# FPGA_Banks1.net
KiCad netlist of a schematic drawn in Altium Designer
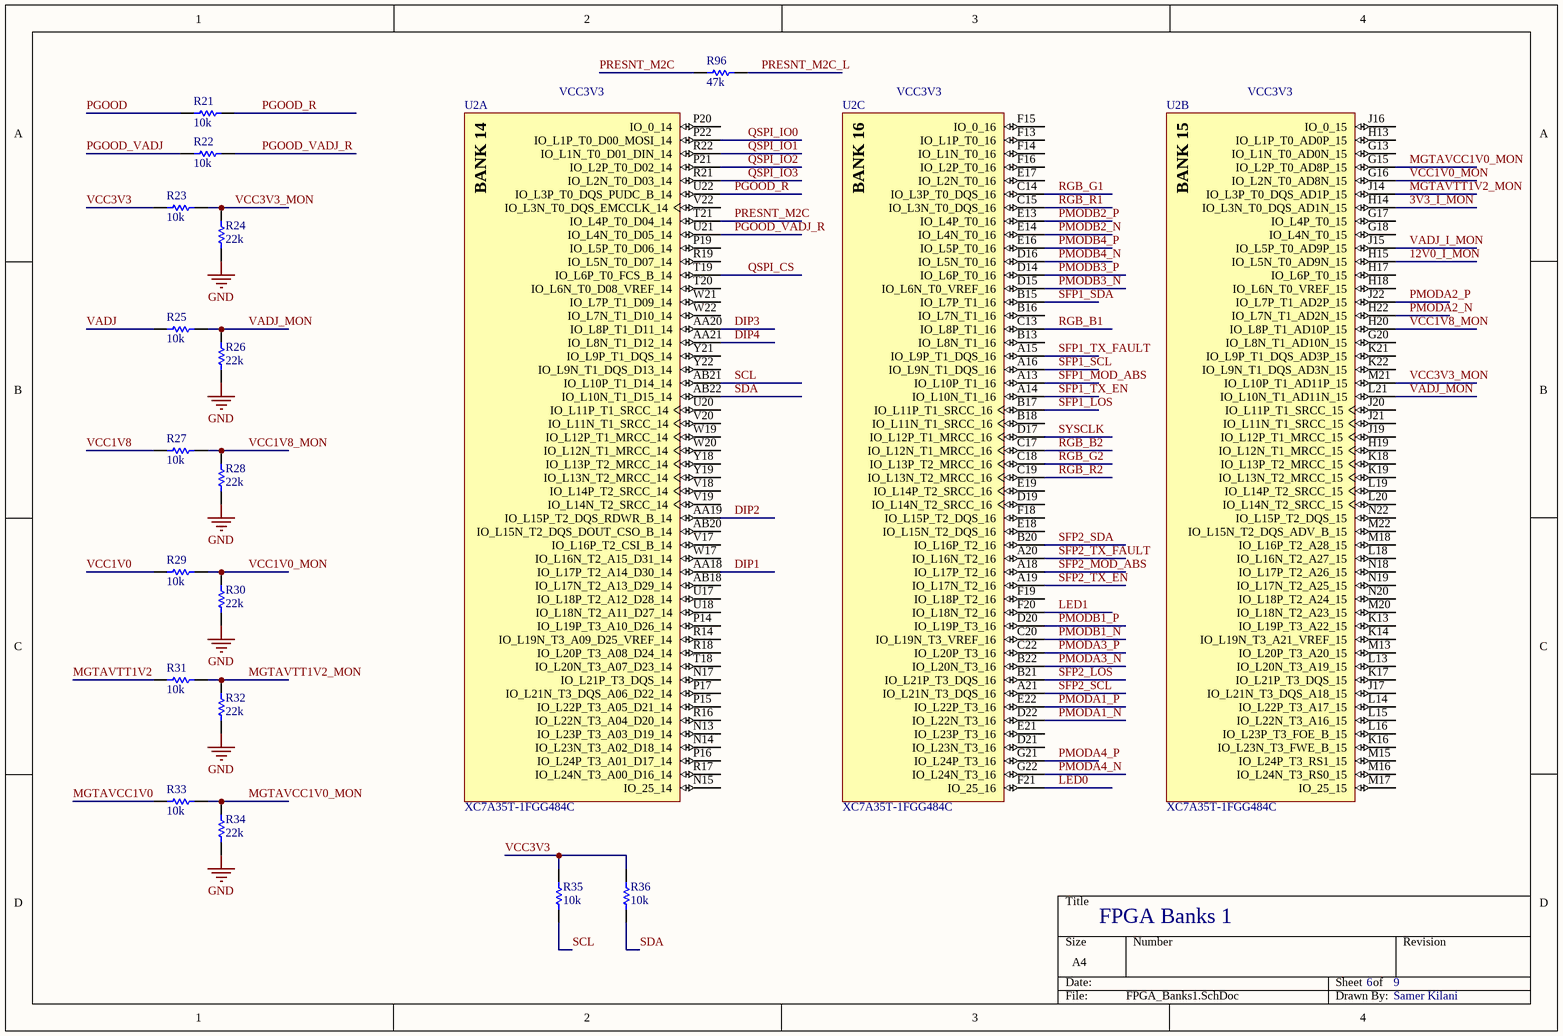
[diagram p0: FPGA_Banks1.SchDoc]

(export (version "E")
  (design (tool "Eeschema 10.0.6"))
  (components
    (comp (ref "R21")
      (value "10k")
      (footprint "R0402")
      (description "Resistor")
      (fields (field (name "Comment") "Res"))
      (libsource (lib "atfclib") (part "Res"))
    )
    (comp (ref "R22")
      (value "10k")
      (footprint "R0402")
      (description "Resistor")
      (fields (field (name "Comment") "Res"))
      (libsource (lib "atfclib") (part "Res"))
    )
    (comp (ref "R23")
      (value "10k")
      (footprint "R0402")
      (description "Resistor")
      (fields (field (name "Comment") "Res"))
      (libsource (lib "atfclib") (part "Res"))
    )
    (comp (ref "R24")
      (value "22k")
      (footprint "R0402")
      (description "Resistor")
      (fields (field (name "Comment") "Res"))
      (libsource (lib "atfclib") (part "Res"))
    )
    (comp (ref "R25")
      (value "10k")
      (footprint "R0402")
      (description "Resistor")
      (fields (field (name "Comment") "Res"))
      (libsource (lib "atfclib") (part "Res"))
    )
    (comp (ref "R26")
      (value "22k")
      (footprint "R0402")
      (description "Resistor")
      (fields (field (name "Comment") "Res"))
      (libsource (lib "atfclib") (part "Res"))
    )
    (comp (ref "R27")
      (value "10k")
      (footprint "R0402")
      (description "Resistor")
      (fields (field (name "Comment") "Res"))
      (libsource (lib "atfclib") (part "Res"))
    )
    (comp (ref "R28")
      (value "22k")
      (footprint "R0402")
      (description "Resistor")
      (fields (field (name "Comment") "Res"))
      (libsource (lib "atfclib") (part "Res"))
    )
    (comp (ref "R29")
      (value "10k")
      (footprint "R0402")
      (description "Resistor")
      (fields (field (name "Comment") "Res"))
      (libsource (lib "atfclib") (part "Res"))
    )
    (comp (ref "R30")
      (value "22k")
      (footprint "R0402")
      (description "Resistor")
      (fields (field (name "Comment") "Res"))
      (libsource (lib "atfclib") (part "Res"))
    )
    (comp (ref "R31")
      (value "10k")
      (footprint "R0402")
      (description "Resistor")
      (fields (field (name "Comment") "Res"))
      (libsource (lib "atfclib") (part "Res"))
    )
    (comp (ref "R32")
      (value "22k")
      (footprint "R0402")
      (description "Resistor")
      (fields (field (name "Comment") "Res"))
      (libsource (lib "atfclib") (part "Res"))
    )
    (comp (ref "R33")
      (value "10k")
      (footprint "R0402")
      (description "Resistor")
      (fields (field (name "Comment") "Res"))
      (libsource (lib "atfclib") (part "Res"))
    )
    (comp (ref "R34")
      (value "22k")
      (footprint "R0402")
      (description "Resistor")
      (fields (field (name "Comment") "Res"))
      (libsource (lib "atfclib") (part "Res"))
    )
    (comp (ref "R35")
      (value "10k")
      (footprint "R0402")
      (description "Resistor")
      (fields (field (name "Comment") "Res"))
      (libsource (lib "atfclib") (part "Res"))
    )
    (comp (ref "R36")
      (value "10k")
      (footprint "R0402")
      (description "Resistor")
      (fields (field (name "Comment") "Res"))
      (libsource (lib "atfclib") (part "Res"))
    )
    (comp (ref "R96")
      (value "47k")
      (footprint "R0402")
      (description "Resistor")
      (fields (field (name "Comment") "Res"))
      (libsource (lib "atfclib") (part "Res"))
    )
    (comp (ref "U2")
      (value "XC7A35T-1FGG484C")
      (footprint "FGG484")
      (description "Artix-7 FPGA, 250 User I/Os, 4 GTP, 484-Ball BGA, Speed Grade 1, Commercial Grade, Pb-Free")
      (fields (field (name "MANUFACTURER") "Xilinx"))
      (libsource (lib "atfclib") (part "XC7A35T-1FGG484C"))
    )
  )
  (nets
    (net (code "1") (name "/3V3_I_MON") (class "Default")
      (node (ref "U2") (pin "H14") (pinfunction "IO_L3N_T0_DQS_AD1N_15_H14") (pintype "bidirectional"))
    )
    (net (code "2") (name "/12V0_I_MON") (class "Default")
      (node (ref "U2") (pin "H15") (pinfunction "IO_L5N_T0_AD9N_15_H15") (pintype "bidirectional"))
    )
    (net (code "3") (name "/DIP1") (class "Default")
      (node (ref "U2") (pin "AA18") (pinfunction "IO_L17P_T2_A14_D30_14_AA18") (pintype "bidirectional"))
    )
    (net (code "4") (name "/DIP2") (class "Default")
      (node (ref "U2") (pin "AA19") (pinfunction "IO_L15P_T2_DQS_RDWR_B_14_AA19") (pintype "bidirectional"))
    )
    (net (code "5") (name "/DIP3") (class "Default")
      (node (ref "U2") (pin "AA20") (pinfunction "IO_L8P_T1_D11_14_AA20") (pintype "bidirectional"))
    )
    (net (code "6") (name "/DIP4") (class "Default")
      (node (ref "U2") (pin "AA21") (pinfunction "IO_L8N_T1_D12_14_AA21") (pintype "bidirectional"))
    )
    (net (code "7") (name "/LED0") (class "Default")
      (node (ref "U2") (pin "F21") (pinfunction "IO_25_16_F21") (pintype "bidirectional"))
    )
    (net (code "8") (name "/LED1") (class "Default")
      (node (ref "U2") (pin "F20") (pinfunction "IO_L18N_T2_16_F20") (pintype "bidirectional"))
    )
    (net (code "9") (name "/MGTAVCC1V0") (class "Default")
      (node (ref "R33") (pin "2") (pinfunction "2_2") (pintype "passive"))
    )
    (net (code "10") (name "/MGTAVCC1V0_MON") (class "Default")
      (node (ref "R33") (pin "1") (pinfunction "1_1") (pintype "passive"))
      (node (ref "R34") (pin "1") (pinfunction "1_1") (pintype "passive"))
      (node (ref "U2") (pin "G15") (pinfunction "IO_L2P_T0_AD8P_15_G15") (pintype "bidirectional"))
    )
    (net (code "11") (name "/MGTAVTT1V2") (class "Default")
      (node (ref "R31") (pin "2") (pinfunction "2_2") (pintype "passive"))
    )
    (net (code "12") (name "/MGTAVTT1V2_MON") (class "Default")
      (node (ref "R31") (pin "1") (pinfunction "1_1") (pintype "passive"))
      (node (ref "R32") (pin "1") (pinfunction "1_1") (pintype "passive"))
      (node (ref "U2") (pin "J14") (pinfunction "IO_L3P_T0_DQS_AD1P_15_J14") (pintype "bidirectional"))
    )
    (net (code "13") (name "/PGOOD") (class "Default")
      (node (ref "R21") (pin "2") (pinfunction "2_2") (pintype "passive"))
    )
    (net (code "14") (name "/PGOOD_R") (class "Default")
      (node (ref "R21") (pin "1") (pinfunction "1_1") (pintype "passive"))
      (node (ref "U2") (pin "U22") (pinfunction "IO_L3P_T0_DQS_PUDC_B_14_U22") (pintype "bidirectional"))
    )
    (net (code "15") (name "/PGOOD_VADJ") (class "Default")
      (node (ref "R22") (pin "2") (pinfunction "2_2") (pintype "passive"))
    )
    (net (code "16") (name "/PGOOD_VADJ_R") (class "Default")
      (node (ref "R22") (pin "1") (pinfunction "1_1") (pintype "passive"))
      (node (ref "U2") (pin "U21") (pinfunction "IO_L4N_T0_D05_14_U21") (pintype "bidirectional"))
    )
    (net (code "17") (name "/PMODA1_N") (class "Default")
      (node (ref "U2") (pin "D22") (pinfunction "IO_L22N_T3_16_D22") (pintype "bidirectional"))
    )
    (net (code "18") (name "/PMODA1_P") (class "Default")
      (node (ref "U2") (pin "E22") (pinfunction "IO_L22P_T3_16_E22") (pintype "bidirectional"))
    )
    (net (code "19") (name "/PMODA2_N") (class "Default")
      (node (ref "U2") (pin "H22") (pinfunction "IO_L7N_T1_AD2N_15_H22") (pintype "bidirectional"))
    )
    (net (code "20") (name "/PMODA2_P") (class "Default")
      (node (ref "U2") (pin "J22") (pinfunction "IO_L7P_T1_AD2P_15_J22") (pintype "bidirectional"))
    )
    (net (code "21") (name "/PMODA3_N") (class "Default")
      (node (ref "U2") (pin "B22") (pinfunction "IO_L20N_T3_16_B22") (pintype "bidirectional"))
    )
    (net (code "22") (name "/PMODA3_P") (class "Default")
      (node (ref "U2") (pin "C22") (pinfunction "IO_L20P_T3_16_C22") (pintype "bidirectional"))
    )
    (net (code "23") (name "/PMODA4_N") (class "Default")
      (node (ref "U2") (pin "G22") (pinfunction "IO_L24N_T3_16_G22") (pintype "bidirectional"))
    )
    (net (code "24") (name "/PMODA4_P") (class "Default")
      (node (ref "U2") (pin "G21") (pinfunction "IO_L24P_T3_16_G21") (pintype "bidirectional"))
    )
    (net (code "25") (name "/PMODB1_N") (class "Default")
      (node (ref "U2") (pin "C20") (pinfunction "IO_L19N_T3_VREF_16_C20") (pintype "bidirectional"))
    )
    (net (code "26") (name "/PMODB1_P") (class "Default")
      (node (ref "U2") (pin "D20") (pinfunction "IO_L19P_T3_16_D20") (pintype "bidirectional"))
    )
    (net (code "27") (name "/PMODB2_N") (class "Default")
      (node (ref "U2") (pin "E14") (pinfunction "IO_L4N_T0_16_E14") (pintype "bidirectional"))
    )
    (net (code "28") (name "/PMODB2_P") (class "Default")
      (node (ref "U2") (pin "E13") (pinfunction "IO_L4P_T0_16_E13") (pintype "bidirectional"))
    )
    (net (code "29") (name "/PMODB3_N") (class "Default")
      (node (ref "U2") (pin "D15") (pinfunction "IO_L6N_T0_VREF_16_D15") (pintype "bidirectional"))
    )
    (net (code "30") (name "/PMODB3_P") (class "Default")
      (node (ref "U2") (pin "D14") (pinfunction "IO_L6P_T0_16_D14") (pintype "bidirectional"))
    )
    (net (code "31") (name "/PMODB4_N") (class "Default")
      (node (ref "U2") (pin "D16") (pinfunction "IO_L5N_T0_16_D16") (pintype "bidirectional"))
    )
    (net (code "32") (name "/PMODB4_P") (class "Default")
      (node (ref "U2") (pin "E16") (pinfunction "IO_L5P_T0_16_E16") (pintype "bidirectional"))
    )
    (net (code "33") (name "/PRESNT_M2C") (class "Default")
      (node (ref "R96") (pin "2") (pinfunction "2_2") (pintype "passive"))
      (node (ref "U2") (pin "T21") (pinfunction "IO_L4P_T0_D04_14_T21") (pintype "bidirectional"))
    )
    (net (code "34") (name "/PRESNT_M2C_L") (class "Default")
      (node (ref "R96") (pin "1") (pinfunction "1_1") (pintype "passive"))
    )
    (net (code "35") (name "/QSPI_CS") (class "Default")
      (node (ref "U2") (pin "T19") (pinfunction "IO_L6P_T0_FCS_B_14_T19") (pintype "bidirectional"))
    )
    (net (code "36") (name "/QSPI_IO0") (class "Default")
      (node (ref "U2") (pin "P22") (pinfunction "IO_L1P_T0_D00_MOSI_14_P22") (pintype "bidirectional"))
    )
    (net (code "37") (name "/QSPI_IO1") (class "Default")
      (node (ref "U2") (pin "R22") (pinfunction "IO_L1N_T0_D01_DIN_14_R22") (pintype "bidirectional"))
    )
    (net (code "38") (name "/QSPI_IO2") (class "Default")
      (node (ref "U2") (pin "P21") (pinfunction "IO_L2P_T0_D02_14_P21") (pintype "bidirectional"))
    )
    (net (code "39") (name "/QSPI_IO3") (class "Default")
      (node (ref "U2") (pin "R21") (pinfunction "IO_L2N_T0_D03_14_R21") (pintype "bidirectional"))
    )
    (net (code "40") (name "/RGB_B1") (class "Default")
      (node (ref "U2") (pin "C13") (pinfunction "IO_L8P_T1_16_C13") (pintype "bidirectional"))
    )
    (net (code "41") (name "/RGB_B2") (class "Default")
      (node (ref "U2") (pin "C17") (pinfunction "IO_L12N_T1_MRCC_16_C17") (pintype "bidirectional"))
    )
    (net (code "42") (name "/RGB_G1") (class "Default")
      (node (ref "U2") (pin "C14") (pinfunction "IO_L3P_T0_DQS_16_C14") (pintype "bidirectional"))
    )
    (net (code "43") (name "/RGB_G2") (class "Default")
      (node (ref "U2") (pin "C18") (pinfunction "IO_L13P_T2_MRCC_16_C18") (pintype "bidirectional"))
    )
    (net (code "44") (name "/RGB_R1") (class "Default")
      (node (ref "U2") (pin "C15") (pinfunction "IO_L3N_T0_DQS_16_C15") (pintype "bidirectional"))
    )
    (net (code "45") (name "/RGB_R2") (class "Default")
      (node (ref "U2") (pin "C19") (pinfunction "IO_L13N_T2_MRCC_16_C19") (pintype "bidirectional"))
    )
    (net (code "46") (name "/SCL") (class "Default")
      (node (ref "R35") (pin "2") (pinfunction "2_2") (pintype "passive"))
      (node (ref "U2") (pin "AB21") (pinfunction "IO_L10P_T1_D14_14_AB21") (pintype "bidirectional"))
    )
    (net (code "47") (name "/SDA") (class "Default")
      (node (ref "R36") (pin "2") (pinfunction "2_2") (pintype "passive"))
      (node (ref "U2") (pin "AB22") (pinfunction "IO_L10N_T1_D15_14_AB22") (pintype "bidirectional"))
    )
    (net (code "48") (name "/SFP1_LOS") (class "Default")
      (node (ref "U2") (pin "B17") (pinfunction "IO_L11P_T1_SRCC_16_B17") (pintype "bidirectional"))
    )
    (net (code "49") (name "/SFP1_MOD_ABS") (class "Default")
      (node (ref "U2") (pin "A13") (pinfunction "IO_L10P_T1_16_A13") (pintype "bidirectional"))
    )
    (net (code "50") (name "/SFP1_SCL") (class "Default")
      (node (ref "U2") (pin "A16") (pinfunction "IO_L9N_T1_DQS_16_A16") (pintype "bidirectional"))
    )
    (net (code "51") (name "/SFP1_SDA") (class "Default")
      (node (ref "U2") (pin "B15") (pinfunction "IO_L7P_T1_16_B15") (pintype "bidirectional"))
    )
    (net (code "52") (name "/SFP1_TX_EN") (class "Default")
      (node (ref "U2") (pin "A14") (pinfunction "IO_L10N_T1_16_A14") (pintype "bidirectional"))
    )
    (net (code "53") (name "/SFP1_TX_FAULT") (class "Default")
      (node (ref "U2") (pin "A15") (pinfunction "IO_L9P_T1_DQS_16_A15") (pintype "bidirectional"))
    )
    (net (code "54") (name "/SFP2_LOS") (class "Default")
      (node (ref "U2") (pin "B21") (pinfunction "IO_L21P_T3_DQS_16_B21") (pintype "bidirectional"))
    )
    (net (code "55") (name "/SFP2_MOD_ABS") (class "Default")
      (node (ref "U2") (pin "A18") (pinfunction "IO_L17P_T2_16_A18") (pintype "bidirectional"))
    )
    (net (code "56") (name "/SFP2_SCL") (class "Default")
      (node (ref "U2") (pin "A21") (pinfunction "IO_L21N_T3_DQS_16_A21") (pintype "bidirectional"))
    )
    (net (code "57") (name "/SFP2_SDA") (class "Default")
      (node (ref "U2") (pin "B20") (pinfunction "IO_L16P_T2_16_B20") (pintype "bidirectional"))
    )
    (net (code "58") (name "/SFP2_TX_EN") (class "Default")
      (node (ref "U2") (pin "A19") (pinfunction "IO_L17N_T2_16_A19") (pintype "bidirectional"))
    )
    (net (code "59") (name "/SFP2_TX_FAULT") (class "Default")
      (node (ref "U2") (pin "A20") (pinfunction "IO_L16N_T2_16_A20") (pintype "bidirectional"))
    )
    (net (code "60") (name "/SYSCLK") (class "Default")
      (node (ref "U2") (pin "D17") (pinfunction "IO_L12P_T1_MRCC_16_D17") (pintype "bidirectional"))
    )
    (net (code "61") (name "/VADJ") (class "Default")
      (node (ref "R25") (pin "2") (pinfunction "2_2") (pintype "passive"))
    )
    (net (code "62") (name "/VADJ_I_MON") (class "Default")
      (node (ref "U2") (pin "J15") (pinfunction "IO_L5P_T0_AD9P_15_J15") (pintype "bidirectional"))
    )
    (net (code "63") (name "/VADJ_MON") (class "Default")
      (node (ref "R25") (pin "1") (pinfunction "1_1") (pintype "passive"))
      (node (ref "R26") (pin "1") (pinfunction "1_1") (pintype "passive"))
      (node (ref "U2") (pin "L21") (pinfunction "IO_L10N_T1_AD11N_15_L21") (pintype "bidirectional"))
    )
    (net (code "64") (name "/VCC1V0") (class "Default")
      (node (ref "R29") (pin "2") (pinfunction "2_2") (pintype "passive"))
    )
    (net (code "65") (name "/VCC1V0_MON") (class "Default")
      (node (ref "R29") (pin "1") (pinfunction "1_1") (pintype "passive"))
      (node (ref "R30") (pin "1") (pinfunction "1_1") (pintype "passive"))
      (node (ref "U2") (pin "G16") (pinfunction "IO_L2N_T0_AD8N_15_G16") (pintype "bidirectional"))
    )
    (net (code "66") (name "/VCC1V8") (class "Default")
      (node (ref "R27") (pin "2") (pinfunction "2_2") (pintype "passive"))
    )
    (net (code "67") (name "/VCC1V8_MON") (class "Default")
      (node (ref "R27") (pin "1") (pinfunction "1_1") (pintype "passive"))
      (node (ref "R28") (pin "1") (pinfunction "1_1") (pintype "passive"))
      (node (ref "U2") (pin "H20") (pinfunction "IO_L8P_T1_AD10P_15_H20") (pintype "bidirectional"))
    )
    (net (code "68") (name "/VCC3V3") (class "Default")
      (node (ref "R23") (pin "2") (pinfunction "2_2") (pintype "passive"))
      (node (ref "R35") (pin "1") (pinfunction "1_1") (pintype "passive"))
      (node (ref "R36") (pin "1") (pinfunction "1_1") (pintype "passive"))
    )
    (net (code "69") (name "/VCC3V3_MON") (class "Default")
      (node (ref "R23") (pin "1") (pinfunction "1_1") (pintype "passive"))
      (node (ref "R24") (pin "1") (pinfunction "1_1") (pintype "passive"))
      (node (ref "U2") (pin "M21") (pinfunction "IO_L10P_T1_AD11P_15_M21") (pintype "bidirectional"))
    )
    (net (code "70") (name "GND") (class "Default")
      (node (ref "R24") (pin "2") (pinfunction "2_2") (pintype "passive"))
      (node (ref "R26") (pin "2") (pinfunction "2_2") (pintype "passive"))
      (node (ref "R28") (pin "2") (pinfunction "2_2") (pintype "passive"))
      (node (ref "R30") (pin "2") (pinfunction "2_2") (pintype "passive"))
      (node (ref "R32") (pin "2") (pinfunction "2_2") (pintype "passive"))
      (node (ref "R34") (pin "2") (pinfunction "2_2") (pintype "passive"))
    )
    (net (code "71") (name "unconnected-(U2A-IO_0_14-PadP20)") (class "Default")
      (node (ref "U2") (pin "P20") (pinfunction "IO_0_14_P20") (pintype "bidirectional"))
    )
    (net (code "72") (name "unconnected-(U2A-IO_25_14-PadN15)") (class "Default")
      (node (ref "U2") (pin "N15") (pinfunction "IO_25_14_N15") (pintype "bidirectional"))
    )
    (net (code "73") (name "unconnected-(U2A-IO_L3N_T0_DQS_EMCCLK_14-PadV22)") (class "Default")
      (node (ref "U2") (pin "V22") (pinfunction "IO_L3N_T0_DQS_EMCCLK_14_V22") (pintype "bidirectional"))
    )
    (net (code "74") (name "unconnected-(U2A-IO_L5N_T0_D07_14-PadR19)") (class "Default")
      (node (ref "U2") (pin "R19") (pinfunction "IO_L5N_T0_D07_14_R19") (pintype "bidirectional"))
    )
    (net (code "75") (name "unconnected-(U2A-IO_L5P_T0_D06_14-PadP19)") (class "Default")
      (node (ref "U2") (pin "P19") (pinfunction "IO_L5P_T0_D06_14_P19") (pintype "bidirectional"))
    )
    (net (code "76") (name "unconnected-(U2A-IO_L6N_T0_D08_VREF_14-PadT20)") (class "Default")
      (node (ref "U2") (pin "T20") (pinfunction "IO_L6N_T0_D08_VREF_14_T20") (pintype "bidirectional"))
    )
    (net (code "77") (name "unconnected-(U2A-IO_L7N_T1_D10_14-PadW22)") (class "Default")
      (node (ref "U2") (pin "W22") (pinfunction "IO_L7N_T1_D10_14_W22") (pintype "bidirectional"))
    )
    (net (code "78") (name "unconnected-(U2A-IO_L7P_T1_D09_14-PadW21)") (class "Default")
      (node (ref "U2") (pin "W21") (pinfunction "IO_L7P_T1_D09_14_W21") (pintype "bidirectional"))
    )
    (net (code "79") (name "unconnected-(U2A-IO_L9N_T1_DQS_D13_14-PadY22)") (class "Default")
      (node (ref "U2") (pin "Y22") (pinfunction "IO_L9N_T1_DQS_D13_14_Y22") (pintype "bidirectional"))
    )
    (net (code "80") (name "unconnected-(U2A-IO_L9P_T1_DQS_14-PadY21)") (class "Default")
      (node (ref "U2") (pin "Y21") (pinfunction "IO_L9P_T1_DQS_14_Y21") (pintype "bidirectional"))
    )
    (net (code "81") (name "unconnected-(U2A-IO_L11N_T1_SRCC_14-PadV20)") (class "Default")
      (node (ref "U2") (pin "V20") (pinfunction "IO_L11N_T1_SRCC_14_V20") (pintype "bidirectional"))
    )
    (net (code "82") (name "unconnected-(U2A-IO_L11P_T1_SRCC_14-PadU20)") (class "Default")
      (node (ref "U2") (pin "U20") (pinfunction "IO_L11P_T1_SRCC_14_U20") (pintype "bidirectional"))
    )
    (net (code "83") (name "unconnected-(U2A-IO_L12N_T1_MRCC_14-PadW20)") (class "Default")
      (node (ref "U2") (pin "W20") (pinfunction "IO_L12N_T1_MRCC_14_W20") (pintype "bidirectional"))
    )
    (net (code "84") (name "unconnected-(U2A-IO_L12P_T1_MRCC_14-PadW19)") (class "Default")
      (node (ref "U2") (pin "W19") (pinfunction "IO_L12P_T1_MRCC_14_W19") (pintype "bidirectional"))
    )
    (net (code "85") (name "unconnected-(U2A-IO_L13N_T2_MRCC_14-PadY19)") (class "Default")
      (node (ref "U2") (pin "Y19") (pinfunction "IO_L13N_T2_MRCC_14_Y19") (pintype "bidirectional"))
    )
    (net (code "86") (name "unconnected-(U2A-IO_L13P_T2_MRCC_14-PadY18)") (class "Default")
      (node (ref "U2") (pin "Y18") (pinfunction "IO_L13P_T2_MRCC_14_Y18") (pintype "bidirectional"))
    )
    (net (code "87") (name "unconnected-(U2A-IO_L14N_T2_SRCC_14-PadV19)") (class "Default")
      (node (ref "U2") (pin "V19") (pinfunction "IO_L14N_T2_SRCC_14_V19") (pintype "bidirectional"))
    )
    (net (code "88") (name "unconnected-(U2A-IO_L14P_T2_SRCC_14-PadV18)") (class "Default")
      (node (ref "U2") (pin "V18") (pinfunction "IO_L14P_T2_SRCC_14_V18") (pintype "bidirectional"))
    )
    (net (code "89") (name "unconnected-(U2A-IO_L15N_T2_DQS_DOUT_CSO_B_14-PadAB20)") (class "Default")
      (node (ref "U2") (pin "AB20") (pinfunction "IO_L15N_T2_DQS_DOUT_CSO_B_14_AB20") (pintype "bidirectional"))
    )
    (net (code "90") (name "unconnected-(U2A-IO_L16N_T2_A15_D31_14-PadW17)") (class "Default")
      (node (ref "U2") (pin "W17") (pinfunction "IO_L16N_T2_A15_D31_14_W17") (pintype "bidirectional"))
    )
    (net (code "91") (name "unconnected-(U2A-IO_L16P_T2_CSI_B_14-PadV17)") (class "Default")
      (node (ref "U2") (pin "V17") (pinfunction "IO_L16P_T2_CSI_B_14_V17") (pintype "bidirectional"))
    )
    (net (code "92") (name "unconnected-(U2A-IO_L17N_T2_A13_D29_14-PadAB18)") (class "Default")
      (node (ref "U2") (pin "AB18") (pinfunction "IO_L17N_T2_A13_D29_14_AB18") (pintype "bidirectional"))
    )
    (net (code "93") (name "unconnected-(U2A-IO_L18N_T2_A11_D27_14-PadU18)") (class "Default")
      (node (ref "U2") (pin "U18") (pinfunction "IO_L18N_T2_A11_D27_14_U18") (pintype "bidirectional"))
    )
    (net (code "94") (name "unconnected-(U2A-IO_L18P_T2_A12_D28_14-PadU17)") (class "Default")
      (node (ref "U2") (pin "U17") (pinfunction "IO_L18P_T2_A12_D28_14_U17") (pintype "bidirectional"))
    )
    (net (code "95") (name "unconnected-(U2A-IO_L19N_T3_A09_D25_VREF_14-PadR14)") (class "Default")
      (node (ref "U2") (pin "R14") (pinfunction "IO_L19N_T3_A09_D25_VREF_14_R14") (pintype "bidirectional"))
    )
    (net (code "96") (name "unconnected-(U2A-IO_L19P_T3_A10_D26_14-PadP14)") (class "Default")
      (node (ref "U2") (pin "P14") (pinfunction "IO_L19P_T3_A10_D26_14_P14") (pintype "bidirectional"))
    )
    (net (code "97") (name "unconnected-(U2A-IO_L20N_T3_A07_D23_14-PadT18)") (class "Default")
      (node (ref "U2") (pin "T18") (pinfunction "IO_L20N_T3_A07_D23_14_T18") (pintype "bidirectional"))
    )
    (net (code "98") (name "unconnected-(U2A-IO_L20P_T3_A08_D24_14-PadR18)") (class "Default")
      (node (ref "U2") (pin "R18") (pinfunction "IO_L20P_T3_A08_D24_14_R18") (pintype "bidirectional"))
    )
    (net (code "99") (name "unconnected-(U2A-IO_L21N_T3_DQS_A06_D22_14-PadP17)") (class "Default")
      (node (ref "U2") (pin "P17") (pinfunction "IO_L21N_T3_DQS_A06_D22_14_P17") (pintype "bidirectional"))
    )
    (net (code "100") (name "unconnected-(U2A-IO_L21P_T3_DQS_14-PadN17)") (class "Default")
      (node (ref "U2") (pin "N17") (pinfunction "IO_L21P_T3_DQS_14_N17") (pintype "bidirectional"))
    )
    (net (code "101") (name "unconnected-(U2A-IO_L22N_T3_A04_D20_14-PadR16)") (class "Default")
      (node (ref "U2") (pin "R16") (pinfunction "IO_L22N_T3_A04_D20_14_R16") (pintype "bidirectional"))
    )
    (net (code "102") (name "unconnected-(U2A-IO_L22P_T3_A05_D21_14-PadP15)") (class "Default")
      (node (ref "U2") (pin "P15") (pinfunction "IO_L22P_T3_A05_D21_14_P15") (pintype "bidirectional"))
    )
    (net (code "103") (name "unconnected-(U2A-IO_L23N_T3_A02_D18_14-PadN14)") (class "Default")
      (node (ref "U2") (pin "N14") (pinfunction "IO_L23N_T3_A02_D18_14_N14") (pintype "bidirectional"))
    )
    (net (code "104") (name "unconnected-(U2A-IO_L23P_T3_A03_D19_14-PadN13)") (class "Default")
      (node (ref "U2") (pin "N13") (pinfunction "IO_L23P_T3_A03_D19_14_N13") (pintype "bidirectional"))
    )
    (net (code "105") (name "unconnected-(U2A-IO_L24N_T3_A00_D16_14-PadR17)") (class "Default")
      (node (ref "U2") (pin "R17") (pinfunction "IO_L24N_T3_A00_D16_14_R17") (pintype "bidirectional"))
    )
    (net (code "106") (name "unconnected-(U2A-IO_L24P_T3_A01_D17_14-PadP16)") (class "Default")
      (node (ref "U2") (pin "P16") (pinfunction "IO_L24P_T3_A01_D17_14_P16") (pintype "bidirectional"))
    )
    (net (code "107") (name "unconnected-(U2B-IO_0_15-PadJ16)") (class "Default")
      (node (ref "U2") (pin "J16") (pinfunction "IO_0_15_J16") (pintype "bidirectional"))
    )
    (net (code "108") (name "unconnected-(U2B-IO_25_15-PadM17)") (class "Default")
      (node (ref "U2") (pin "M17") (pinfunction "IO_25_15_M17") (pintype "bidirectional"))
    )
    (net (code "109") (name "unconnected-(U2B-IO_L1N_T0_AD0N_15-PadG13)") (class "Default")
      (node (ref "U2") (pin "G13") (pinfunction "IO_L1N_T0_AD0N_15_G13") (pintype "bidirectional"))
    )
    (net (code "110") (name "unconnected-(U2B-IO_L1P_T0_AD0P_15-PadH13)") (class "Default")
      (node (ref "U2") (pin "H13") (pinfunction "IO_L1P_T0_AD0P_15_H13") (pintype "bidirectional"))
    )
    (net (code "111") (name "unconnected-(U2B-IO_L4N_T0_15-PadG18)") (class "Default")
      (node (ref "U2") (pin "G18") (pinfunction "IO_L4N_T0_15_G18") (pintype "bidirectional"))
    )
    (net (code "112") (name "unconnected-(U2B-IO_L4P_T0_15-PadG17)") (class "Default")
      (node (ref "U2") (pin "G17") (pinfunction "IO_L4P_T0_15_G17") (pintype "bidirectional"))
    )
    (net (code "113") (name "unconnected-(U2B-IO_L6N_T0_VREF_15-PadH18)") (class "Default")
      (node (ref "U2") (pin "H18") (pinfunction "IO_L6N_T0_VREF_15_H18") (pintype "bidirectional"))
    )
    (net (code "114") (name "unconnected-(U2B-IO_L6P_T0_15-PadH17)") (class "Default")
      (node (ref "U2") (pin "H17") (pinfunction "IO_L6P_T0_15_H17") (pintype "bidirectional"))
    )
    (net (code "115") (name "unconnected-(U2B-IO_L8N_T1_AD10N_15-PadG20)") (class "Default")
      (node (ref "U2") (pin "G20") (pinfunction "IO_L8N_T1_AD10N_15_G20") (pintype "bidirectional"))
    )
    (net (code "116") (name "unconnected-(U2B-IO_L9N_T1_DQS_AD3N_15-PadK22)") (class "Default")
      (node (ref "U2") (pin "K22") (pinfunction "IO_L9N_T1_DQS_AD3N_15_K22") (pintype "bidirectional"))
    )
    (net (code "117") (name "unconnected-(U2B-IO_L9P_T1_DQS_AD3P_15-PadK21)") (class "Default")
      (node (ref "U2") (pin "K21") (pinfunction "IO_L9P_T1_DQS_AD3P_15_K21") (pintype "bidirectional"))
    )
    (net (code "118") (name "unconnected-(U2B-IO_L11N_T1_SRCC_15-PadJ21)") (class "Default")
      (node (ref "U2") (pin "J21") (pinfunction "IO_L11N_T1_SRCC_15_J21") (pintype "bidirectional"))
    )
    (net (code "119") (name "unconnected-(U2B-IO_L11P_T1_SRCC_15-PadJ20)") (class "Default")
      (node (ref "U2") (pin "J20") (pinfunction "IO_L11P_T1_SRCC_15_J20") (pintype "bidirectional"))
    )
    (net (code "120") (name "unconnected-(U2B-IO_L12N_T1_MRCC_15-PadH19)") (class "Default")
      (node (ref "U2") (pin "H19") (pinfunction "IO_L12N_T1_MRCC_15_H19") (pintype "bidirectional"))
    )
    (net (code "121") (name "unconnected-(U2B-IO_L12P_T1_MRCC_15-PadJ19)") (class "Default")
      (node (ref "U2") (pin "J19") (pinfunction "IO_L12P_T1_MRCC_15_J19") (pintype "bidirectional"))
    )
    (net (code "122") (name "unconnected-(U2B-IO_L13N_T2_MRCC_15-PadK19)") (class "Default")
      (node (ref "U2") (pin "K19") (pinfunction "IO_L13N_T2_MRCC_15_K19") (pintype "bidirectional"))
    )
    (net (code "123") (name "unconnected-(U2B-IO_L13P_T2_MRCC_15-PadK18)") (class "Default")
      (node (ref "U2") (pin "K18") (pinfunction "IO_L13P_T2_MRCC_15_K18") (pintype "bidirectional"))
    )
    (net (code "124") (name "unconnected-(U2B-IO_L14N_T2_SRCC_15-PadL20)") (class "Default")
      (node (ref "U2") (pin "L20") (pinfunction "IO_L14N_T2_SRCC_15_L20") (pintype "bidirectional"))
    )
    (net (code "125") (name "unconnected-(U2B-IO_L14P_T2_SRCC_15-PadL19)") (class "Default")
      (node (ref "U2") (pin "L19") (pinfunction "IO_L14P_T2_SRCC_15_L19") (pintype "bidirectional"))
    )
    (net (code "126") (name "unconnected-(U2B-IO_L15N_T2_DQS_ADV_B_15-PadM22)") (class "Default")
      (node (ref "U2") (pin "M22") (pinfunction "IO_L15N_T2_DQS_ADV_B_15_M22") (pintype "bidirectional"))
    )
    (net (code "127") (name "unconnected-(U2B-IO_L15P_T2_DQS_15-PadN22)") (class "Default")
      (node (ref "U2") (pin "N22") (pinfunction "IO_L15P_T2_DQS_15_N22") (pintype "bidirectional"))
    )
    (net (code "128") (name "unconnected-(U2B-IO_L16N_T2_A27_15-PadL18)") (class "Default")
      (node (ref "U2") (pin "L18") (pinfunction "IO_L16N_T2_A27_15_L18") (pintype "bidirectional"))
    )
    (net (code "129") (name "unconnected-(U2B-IO_L16P_T2_A28_15-PadM18)") (class "Default")
      (node (ref "U2") (pin "M18") (pinfunction "IO_L16P_T2_A28_15_M18") (pintype "bidirectional"))
    )
    (net (code "130") (name "unconnected-(U2B-IO_L17N_T2_A25_15-PadN19)") (class "Default")
      (node (ref "U2") (pin "N19") (pinfunction "IO_L17N_T2_A25_15_N19") (pintype "bidirectional"))
    )
    (net (code "131") (name "unconnected-(U2B-IO_L17P_T2_A26_15-PadN18)") (class "Default")
      (node (ref "U2") (pin "N18") (pinfunction "IO_L17P_T2_A26_15_N18") (pintype "bidirectional"))
    )
    (net (code "132") (name "unconnected-(U2B-IO_L18N_T2_A23_15-PadM20)") (class "Default")
      (node (ref "U2") (pin "M20") (pinfunction "IO_L18N_T2_A23_15_M20") (pintype "bidirectional"))
    )
    (net (code "133") (name "unconnected-(U2B-IO_L18P_T2_A24_15-PadN20)") (class "Default")
      (node (ref "U2") (pin "N20") (pinfunction "IO_L18P_T2_A24_15_N20") (pintype "bidirectional"))
    )
    (net (code "134") (name "unconnected-(U2B-IO_L19N_T3_A21_VREF_15-PadK14)") (class "Default")
      (node (ref "U2") (pin "K14") (pinfunction "IO_L19N_T3_A21_VREF_15_K14") (pintype "bidirectional"))
    )
    (net (code "135") (name "unconnected-(U2B-IO_L19P_T3_A22_15-PadK13)") (class "Default")
      (node (ref "U2") (pin "K13") (pinfunction "IO_L19P_T3_A22_15_K13") (pintype "bidirectional"))
    )
    (net (code "136") (name "unconnected-(U2B-IO_L20N_T3_A19_15-PadL13)") (class "Default")
      (node (ref "U2") (pin "L13") (pinfunction "IO_L20N_T3_A19_15_L13") (pintype "bidirectional"))
    )
    (net (code "137") (name "unconnected-(U2B-IO_L20P_T3_A20_15-PadM13)") (class "Default")
      (node (ref "U2") (pin "M13") (pinfunction "IO_L20P_T3_A20_15_M13") (pintype "bidirectional"))
    )
    (net (code "138") (name "unconnected-(U2B-IO_L21N_T3_DQS_A18_15-PadJ17)") (class "Default")
      (node (ref "U2") (pin "J17") (pinfunction "IO_L21N_T3_DQS_A18_15_J17") (pintype "bidirectional"))
    )
    (net (code "139") (name "unconnected-(U2B-IO_L21P_T3_DQS_15-PadK17)") (class "Default")
      (node (ref "U2") (pin "K17") (pinfunction "IO_L21P_T3_DQS_15_K17") (pintype "bidirectional"))
    )
    (net (code "140") (name "unconnected-(U2B-IO_L22N_T3_A16_15-PadL15)") (class "Default")
      (node (ref "U2") (pin "L15") (pinfunction "IO_L22N_T3_A16_15_L15") (pintype "bidirectional"))
    )
    (net (code "141") (name "unconnected-(U2B-IO_L22P_T3_A17_15-PadL14)") (class "Default")
      (node (ref "U2") (pin "L14") (pinfunction "IO_L22P_T3_A17_15_L14") (pintype "bidirectional"))
    )
    (net (code "142") (name "unconnected-(U2B-IO_L23N_T3_FWE_B_15-PadK16)") (class "Default")
      (node (ref "U2") (pin "K16") (pinfunction "IO_L23N_T3_FWE_B_15_K16") (pintype "bidirectional"))
    )
    (net (code "143") (name "unconnected-(U2B-IO_L23P_T3_FOE_B_15-PadL16)") (class "Default")
      (node (ref "U2") (pin "L16") (pinfunction "IO_L23P_T3_FOE_B_15_L16") (pintype "bidirectional"))
    )
    (net (code "144") (name "unconnected-(U2B-IO_L24N_T3_RS0_15-PadM16)") (class "Default")
      (node (ref "U2") (pin "M16") (pinfunction "IO_L24N_T3_RS0_15_M16") (pintype "bidirectional"))
    )
    (net (code "145") (name "unconnected-(U2B-IO_L24P_T3_RS1_15-PadM15)") (class "Default")
      (node (ref "U2") (pin "M15") (pinfunction "IO_L24P_T3_RS1_15_M15") (pintype "bidirectional"))
    )
    (net (code "146") (name "unconnected-(U2C-IO_0_16-PadF15)") (class "Default")
      (node (ref "U2") (pin "F15") (pinfunction "IO_0_16_F15") (pintype "bidirectional"))
    )
    (net (code "147") (name "unconnected-(U2C-IO_L1N_T0_16-PadF14)") (class "Default")
      (node (ref "U2") (pin "F14") (pinfunction "IO_L1N_T0_16_F14") (pintype "bidirectional"))
    )
    (net (code "148") (name "unconnected-(U2C-IO_L1P_T0_16-PadF13)") (class "Default")
      (node (ref "U2") (pin "F13") (pinfunction "IO_L1P_T0_16_F13") (pintype "bidirectional"))
    )
    (net (code "149") (name "unconnected-(U2C-IO_L2N_T0_16-PadE17)") (class "Default")
      (node (ref "U2") (pin "E17") (pinfunction "IO_L2N_T0_16_E17") (pintype "bidirectional"))
    )
    (net (code "150") (name "unconnected-(U2C-IO_L2P_T0_16-PadF16)") (class "Default")
      (node (ref "U2") (pin "F16") (pinfunction "IO_L2P_T0_16_F16") (pintype "bidirectional"))
    )
    (net (code "151") (name "unconnected-(U2C-IO_L7N_T1_16-PadB16)") (class "Default")
      (node (ref "U2") (pin "B16") (pinfunction "IO_L7N_T1_16_B16") (pintype "bidirectional"))
    )
    (net (code "152") (name "unconnected-(U2C-IO_L8N_T1_16-PadB13)") (class "Default")
      (node (ref "U2") (pin "B13") (pinfunction "IO_L8N_T1_16_B13") (pintype "bidirectional"))
    )
    (net (code "153") (name "unconnected-(U2C-IO_L11N_T1_SRCC_16-PadB18)") (class "Default")
      (node (ref "U2") (pin "B18") (pinfunction "IO_L11N_T1_SRCC_16_B18") (pintype "bidirectional"))
    )
    (net (code "154") (name "unconnected-(U2C-IO_L14N_T2_SRCC_16-PadD19)") (class "Default")
      (node (ref "U2") (pin "D19") (pinfunction "IO_L14N_T2_SRCC_16_D19") (pintype "bidirectional"))
    )
    (net (code "155") (name "unconnected-(U2C-IO_L14P_T2_SRCC_16-PadE19)") (class "Default")
      (node (ref "U2") (pin "E19") (pinfunction "IO_L14P_T2_SRCC_16_E19") (pintype "bidirectional"))
    )
    (net (code "156") (name "unconnected-(U2C-IO_L15N_T2_DQS_16-PadE18)") (class "Default")
      (node (ref "U2") (pin "E18") (pinfunction "IO_L15N_T2_DQS_16_E18") (pintype "bidirectional"))
    )
    (net (code "157") (name "unconnected-(U2C-IO_L15P_T2_DQS_16-PadF18)") (class "Default")
      (node (ref "U2") (pin "F18") (pinfunction "IO_L15P_T2_DQS_16_F18") (pintype "bidirectional"))
    )
    (net (code "158") (name "unconnected-(U2C-IO_L18P_T2_16-PadF19)") (class "Default")
      (node (ref "U2") (pin "F19") (pinfunction "IO_L18P_T2_16_F19") (pintype "bidirectional"))
    )
    (net (code "159") (name "unconnected-(U2C-IO_L23N_T3_16-PadD21)") (class "Default")
      (node (ref "U2") (pin "D21") (pinfunction "IO_L23N_T3_16_D21") (pintype "bidirectional"))
    )
    (net (code "160") (name "unconnected-(U2C-IO_L23P_T3_16-PadE21)") (class "Default")
      (node (ref "U2") (pin "E21") (pinfunction "IO_L23P_T3_16_E21") (pintype "bidirectional"))
    )
  )
)
